# SD_Card.net
KiCad netlist of a schematic drawn in Altium Designer
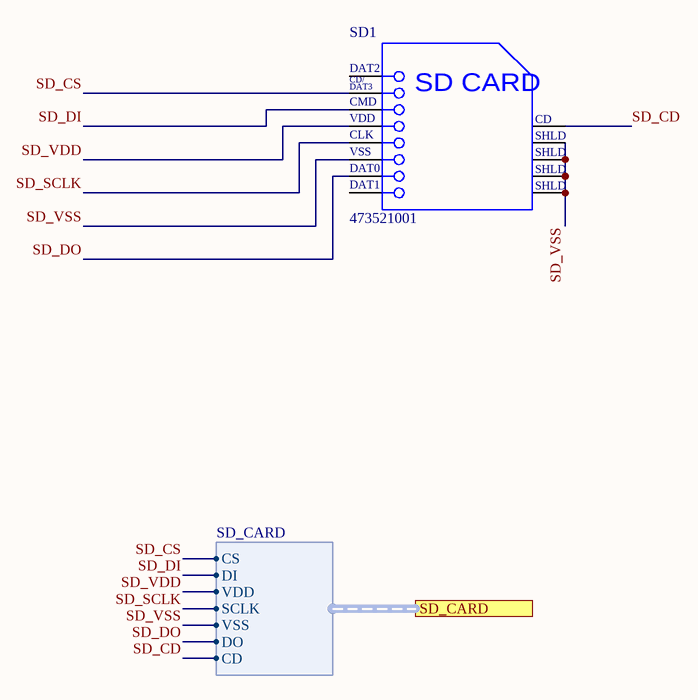
[diagram p0: SD_Card.SchDoc]

(export (version "E")
  (design (tool "Eeschema 10.0.6"))
  (components
    (comp (ref "SD1")
      (value "473521001")
      (footprint "MOLX-473521001_V")
      (description "MicroSD(TM), Pitch 1.1 mm, 8 Position, Height 1.88 mm, -20 to 85 degC, RoHS, Tape and Reel")
      (fields (field (name "MANUFACTURER") "Molex"))
      (libsource (lib "Altium Content Vault") (part "CN-SD-8-1SW-4S"))
    )
  )
  (nets
    (net (code "2") (name "/SD_CD") (class "Default")
      (node (ref "SD1") (pin "9") (pinfunction "CD_9") (pintype "passive"))
    )
    (net (code "3") (name "/SD_CS") (class "Default")
      (node (ref "SD1") (pin "2") (pinfunction "CD/DAT3_2") (pintype "passive"))
    )
    (net (code "4") (name "/SD_DI") (class "Default")
      (node (ref "SD1") (pin "3") (pinfunction "CMD_3") (pintype "passive"))
    )
    (net (code "5") (name "/SD_DO") (class "Default")
      (node (ref "SD1") (pin "7") (pinfunction "DAT0_7") (pintype "passive"))
    )
    (net (code "6") (name "/SD_SCLK") (class "Default")
      (node (ref "SD1") (pin "5") (pinfunction "CLK_5") (pintype "passive"))
    )
    (net (code "7") (name "/SD_VDD") (class "Default")
      (node (ref "SD1") (pin "4") (pinfunction "VDD_4") (pintype "passive"))
    )
    (net (code "8") (name "/SD_VSS") (class "Default")
      (node (ref "SD1") (pin "10") (pinfunction "SHLD_10") (pintype "passive"))
      (node (ref "SD1") (pin "11") (pinfunction "SHLD_11") (pintype "passive"))
      (node (ref "SD1") (pin "12") (pinfunction "SHLD_12") (pintype "passive"))
      (node (ref "SD1") (pin "13") (pinfunction "SHLD_13") (pintype "passive"))
      (node (ref "SD1") (pin "6") (pinfunction "VSS_6") (pintype "passive"))
    )
    (net (code "10") (name "unconnected-(SD1-DAT1-Pad8)") (class "Default")
      (node (ref "SD1") (pin "8") (pinfunction "DAT1_8") (pintype "passive"))
    )
    (net (code "11") (name "unconnected-(SD1-DAT2-Pad1)") (class "Default")
      (node (ref "SD1") (pin "1") (pinfunction "DAT2_1") (pintype "passive"))
    )
  )
)
